# Top.net
KiCad netlist of a schematic drawn in Altium Designer
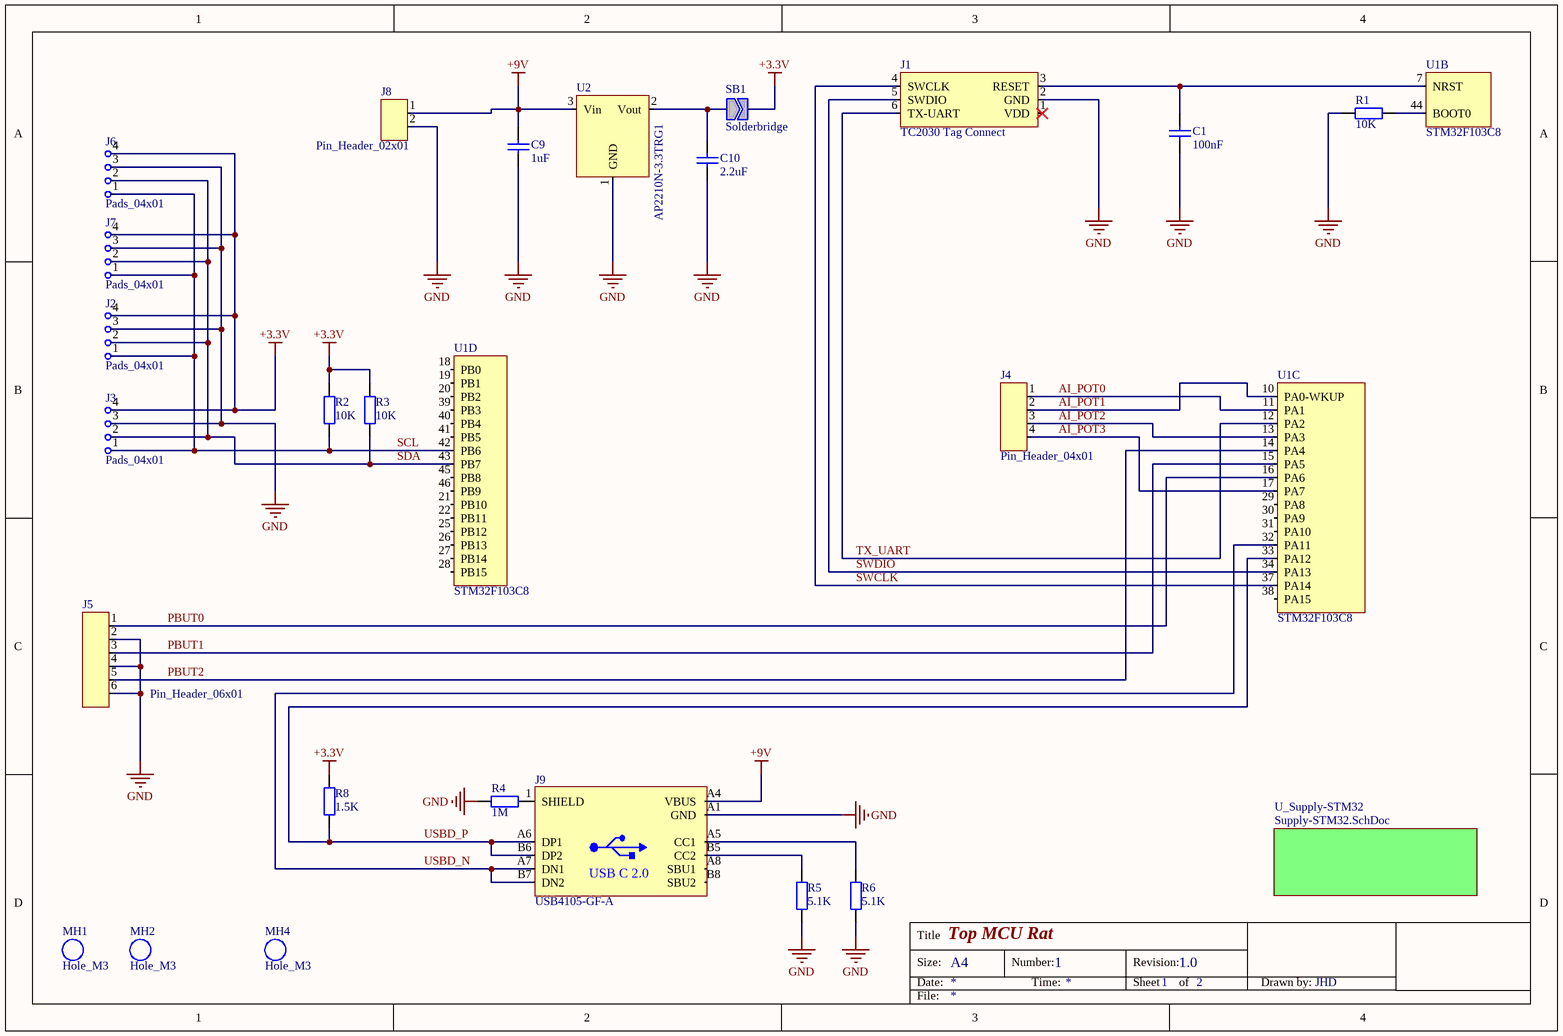
[diagram p0: Top.SchDoc]

(export (version "E")
  (design (tool "Eeschema 10.0.6"))
  (components
    (comp (ref "C1")
      (value "100nF")
      (footprint "CAP_0603")
      (fields (field (name "Comment") "CAP"))
      (libsource (lib "Passive") (part "CAP"))
    )
    (comp (ref "C9")
      (value "1uF")
      (footprint "CAP_0603")
      (fields (field (name "Comment") "CAP"))
      (libsource (lib "") (part "CAP_1"))
    )
    (comp (ref "C10")
      (value "2.2uF")
      (footprint "CAP_0603")
      (fields (field (name "Comment") "CAP"))
      (libsource (lib "") (part "CAP_1"))
    )
    (comp (ref "J1")
      (value "TC2030 Tag Connect")
      (footprint "TC2030-MCP")
      (libsource (lib "Connectors") (part "TC2030"))
    )
    (comp (ref "J2")
      (value "Pads_04x01")
      (footprint "04X01_PADS_2.54MM")
      (libsource (lib "Connectors") (part "Pads_04x01"))
    )
    (comp (ref "J3")
      (value "Pads_04x01")
      (footprint "04X01_PADS_2.54MM")
      (libsource (lib "Connectors") (part "Pads_04x01"))
    )
    (comp (ref "J4")
      (value "Pin_Header_04x01")
      (footprint "04x01_Header_2.54mm_MAL")
      (libsource (lib "Connectors") (part "Pin_Header_04x01"))
    )
    (comp (ref "J5")
      (value "Pin_Header_06x01")
      (footprint "06X01_TERM_5.00MM_FEM_DOWN")
      (libsource (lib "Connectors") (part "Pin_Header_06x01"))
    )
    (comp (ref "J6")
      (value "Pads_04x01")
      (footprint "04X01_PADS_2.54MM")
      (libsource (lib "Connectors") (part "Pads_04x01"))
    )
    (comp (ref "J7")
      (value "Pads_04x01")
      (footprint "04X01_PADS_2.54MM")
      (libsource (lib "Connectors") (part "Pads_04x01"))
    )
    (comp (ref "J8")
      (value "Pin_Header_02x01")
      (footprint "02X01_TERM_5.00MM_FEM_DOWN")
      (libsource (lib "Connectors") (part "Pin_Header_02x01"))
    )
    (comp (ref "J9")
      (value "USB4105-GF-A")
      (footprint "USB4105-GF-A")
      (description "USB Connectors USB Type C,2.0, Rec,SMT, 0.95mmTH Shell Stakes,G/F,RA,Top Mnt,T&R")
      (libsource (lib "GCT") (part "USB4105-GF-A"))
    )
    (comp (ref "MH1") (value "Hole_M3") (footprint "Hole_M3") (libsource (lib "Holes") (part "Hole_M3")))
    (comp (ref "MH2") (value "Hole_M3") (footprint "Hole_M3") (libsource (lib "Holes") (part "Hole_M3")))
    (comp (ref "MH4") (value "Hole_M3") (footprint "Hole_M3") (libsource (lib "Holes") (part "Hole_M3")))
    (comp (ref "R1")
      (value "10K")
      (footprint "RES_0603")
      (fields (field (name "Comment") "RES"))
      (libsource (lib "Passive") (part "RES"))
    )
    (comp (ref "R2")
      (value "10K")
      (footprint "RES_0603")
      (fields (field (name "Comment") "RES"))
      (libsource (lib "") (part "RES_1"))
    )
    (comp (ref "R3")
      (value "10K")
      (footprint "RES_0603")
      (fields (field (name "Comment") "RES"))
      (libsource (lib "") (part "RES_1"))
    )
    (comp (ref "R4")
      (value "1M")
      (footprint "RES_0603")
      (fields (field (name "Comment") "RES"))
      (libsource (lib "Passive") (part "RES"))
    )
    (comp (ref "R5")
      (value "5.1K")
      (footprint "RES_0603")
      (fields (field (name "Comment") "RES"))
      (libsource (lib "") (part "RES_1"))
    )
    (comp (ref "R6")
      (value "5.1K")
      (footprint "RES_0603")
      (fields (field (name "Comment") "RES"))
      (libsource (lib "") (part "RES_1"))
    )
    (comp (ref "R8")
      (value "1.5K")
      (footprint "RES_0603")
      (fields (field (name "Comment") "RES"))
      (libsource (lib "") (part "RES_1"))
    )
    (comp (ref "SB1")
      (value "Solderbridge")
      (footprint "TRIAN SOLDERBRIDGE")
      (libsource (lib "SolderJumper") (part "Solderbridge"))
    )
    (comp (ref "U1")
      (value "STM32F103C8")
      (footprint "LQFP48P05S97X97")
      (fields (field (name "MANUFACTURER") "STMicroelectronics"))
      (libsource (lib "ST") (part "STM32F103C8"))
    )
    (comp (ref "U2")
      (value "AP2210N-3.3TRG1")
      (footprint "SOT-23-3")
      (fields (field (name "MANUFACTURER") "Diodes Incorperated"))
      (libsource (lib "Diodes Incorporated") (part "AP2210N-3.3TRG1"))
    )
  )
  (nets
    (net (code "1") (name "+3.3V") (class "Default")
      (node (ref "J2") (pin "4") (pintype "passive"))
      (node (ref "J3") (pin "4") (pintype "passive"))
      (node (ref "J6") (pin "4") (pintype "passive"))
      (node (ref "J7") (pin "4") (pintype "passive"))
      (node (ref "R2") (pin "2") (pinfunction "2_2") (pintype "passive"))
      (node (ref "R3") (pin "2") (pinfunction "2_2") (pintype "passive"))
      (node (ref "R8") (pin "2") (pinfunction "2_2") (pintype "passive"))
      (node (ref "SB1") (pin "2") (pinfunction "2_2") (pintype "passive"))
    )
    (net (code "2") (name "+9V") (class "Default")
      (node (ref "C9") (pin "2") (pinfunction "2_2") (pintype "passive"))
      (node (ref "J8") (pin "1") (pintype "passive"))
      (node (ref "J9") (pin "A4") (pinfunction "VBUS_A4") (pintype "power_in"))
      (node (ref "U2") (pin "3") (pinfunction "Vin_3") (pintype "power_in"))
    )
    (net (code "3") (name "/AI_POT0") (class "Default")
      (node (ref "J4") (pin "1") (pintype "passive"))
      (node (ref "U1") (pin "11") (pinfunction "PA1_11") (pintype "bidirectional"))
    )
    (net (code "4") (name "/AI_POT1") (class "Default")
      (node (ref "J4") (pin "2") (pintype "passive"))
      (node (ref "U1") (pin "10") (pinfunction "PA0-WKUP_10") (pintype "bidirectional"))
    )
    (net (code "5") (name "/AI_POT2") (class "Default")
      (node (ref "J4") (pin "3") (pintype "passive"))
      (node (ref "U1") (pin "13") (pinfunction "PA3_13") (pintype "bidirectional"))
    )
    (net (code "6") (name "/AI_POT3") (class "Default")
      (node (ref "J4") (pin "4") (pintype "passive"))
      (node (ref "U1") (pin "17") (pinfunction "PA7_17") (pintype "bidirectional"))
    )
    (net (code "7") (name "/PBUT0") (class "Default")
      (node (ref "J5") (pin "1") (pintype "passive"))
      (node (ref "U1") (pin "16") (pinfunction "PA6_16") (pintype "bidirectional"))
    )
    (net (code "8") (name "/PBUT1") (class "Default")
      (node (ref "J5") (pin "3") (pintype "passive"))
      (node (ref "U1") (pin "15") (pinfunction "PA5_15") (pintype "bidirectional"))
    )
    (net (code "9") (name "/PBUT2") (class "Default")
      (node (ref "J5") (pin "5") (pintype "passive"))
      (node (ref "U1") (pin "14") (pinfunction "PA4_14") (pintype "bidirectional"))
    )
    (net (code "10") (name "/SCL") (class "Default")
      (node (ref "J2") (pin "1") (pintype "passive"))
      (node (ref "J3") (pin "1") (pintype "passive"))
      (node (ref "J6") (pin "1") (pintype "passive"))
      (node (ref "J7") (pin "1") (pintype "passive"))
      (node (ref "R2") (pin "1") (pinfunction "1_1") (pintype "passive"))
      (node (ref "U1") (pin "42") (pinfunction "PB6_42") (pintype "bidirectional"))
    )
    (net (code "11") (name "/SDA") (class "Default")
      (node (ref "J2") (pin "2") (pintype "passive"))
      (node (ref "J3") (pin "2") (pintype "passive"))
      (node (ref "J6") (pin "2") (pintype "passive"))
      (node (ref "J7") (pin "2") (pintype "passive"))
      (node (ref "R3") (pin "1") (pinfunction "1_1") (pintype "passive"))
      (node (ref "U1") (pin "43") (pinfunction "PB7_43") (pintype "bidirectional"))
    )
    (net (code "12") (name "/SWCLK") (class "Default")
      (node (ref "J1") (pin "4") (pinfunction "SWCLK_4") (pintype "passive"))
      (node (ref "U1") (pin "37") (pinfunction "PA14_37") (pintype "bidirectional"))
    )
    (net (code "13") (name "/SWDIO") (class "Default")
      (node (ref "J1") (pin "5") (pinfunction "SWDIO_5") (pintype "passive"))
      (node (ref "U1") (pin "34") (pinfunction "PA13_34") (pintype "bidirectional"))
    )
    (net (code "14") (name "/TX_UART") (class "Default")
      (node (ref "J1") (pin "6") (pinfunction "TX-UART_6") (pintype "passive"))
      (node (ref "U1") (pin "12") (pinfunction "PA2_12") (pintype "bidirectional"))
    )
    (net (code "15") (name "/USBD_N") (class "Default")
      (node (ref "J9") (pin "A7") (pinfunction "DN1_A7") (pintype "bidirectional"))
      (node (ref "J9") (pin "B7") (pinfunction "DN2_B7") (pintype "bidirectional"))
      (node (ref "U1") (pin "32") (pinfunction "PA11_32") (pintype "bidirectional"))
    )
    (net (code "16") (name "/USBD_P") (class "Default")
      (node (ref "J9") (pin "A6") (pinfunction "DP1_A6") (pintype "bidirectional"))
      (node (ref "J9") (pin "B6") (pinfunction "DP2_B6") (pintype "bidirectional"))
      (node (ref "R8") (pin "1") (pinfunction "1_1") (pintype "passive"))
      (node (ref "U1") (pin "33") (pinfunction "PA12_33") (pintype "bidirectional"))
    )
    (net (code "17") (name "GND") (class "Default")
      (node (ref "C1") (pin "1") (pinfunction "1_1") (pintype "passive"))
      (node (ref "C10") (pin "1") (pinfunction "1_1") (pintype "passive"))
      (node (ref "C9") (pin "1") (pinfunction "1_1") (pintype "passive"))
      (node (ref "J1") (pin "2") (pinfunction "GND_2") (pintype "passive"))
      (node (ref "J2") (pin "3") (pintype "passive"))
      (node (ref "J3") (pin "3") (pintype "passive"))
      (node (ref "J5") (pin "2") (pintype "passive"))
      (node (ref "J5") (pin "4") (pintype "passive"))
      (node (ref "J5") (pin "6") (pintype "passive"))
      (node (ref "J6") (pin "3") (pintype "passive"))
      (node (ref "J7") (pin "3") (pintype "passive"))
      (node (ref "J8") (pin "2") (pintype "passive"))
      (node (ref "J9") (pin "A1") (pinfunction "GND_A1") (pintype "power_in"))
      (node (ref "R1") (pin "2") (pinfunction "2_2") (pintype "passive"))
      (node (ref "R4") (pin "2") (pinfunction "2_2") (pintype "passive"))
      (node (ref "R5") (pin "1") (pinfunction "1_1") (pintype "passive"))
      (node (ref "R6") (pin "1") (pinfunction "1_1") (pintype "passive"))
      (node (ref "U2") (pin "1") (pinfunction "GND_1") (pintype "power_in"))
    )
    (net (code "18") (name "Net-(J1-RESET)") (class "Default")
      (node (ref "C1") (pin "2") (pinfunction "2_2") (pintype "passive"))
      (node (ref "J1") (pin "3") (pinfunction "RESET_3") (pintype "passive"))
      (node (ref "U1") (pin "7") (pinfunction "NRST_7") (pintype "bidirectional"))
    )
    (net (code "19") (name "Net-(J9-CC1)") (class "Default")
      (node (ref "J9") (pin "A5") (pinfunction "CC1_A5") (pintype "passive"))
      (node (ref "R6") (pin "2") (pinfunction "2_2") (pintype "passive"))
    )
    (net (code "20") (name "Net-(J9-CC2)") (class "Default")
      (node (ref "J9") (pin "B5") (pinfunction "CC2_B5") (pintype "passive"))
      (node (ref "R5") (pin "2") (pinfunction "2_2") (pintype "passive"))
    )
    (net (code "21") (name "Net-(J9-SHIELD)") (class "Default")
      (node (ref "J9") (pin "1") (pinfunction "SHIELD_1") (pintype "passive"))
      (node (ref "R4") (pin "1") (pinfunction "1_1") (pintype "passive"))
    )
    (net (code "22") (name "Net-(U1B-BOOT0)") (class "Default")
      (node (ref "R1") (pin "1") (pinfunction "1_1") (pintype "passive"))
      (node (ref "U1") (pin "44") (pinfunction "BOOT0_44") (pintype "input"))
    )
    (net (code "23") (name "Net-(U2-Vout)") (class "Default")
      (node (ref "C10") (pin "2") (pinfunction "2_2") (pintype "passive"))
      (node (ref "SB1") (pin "1") (pinfunction "1_1") (pintype "passive"))
      (node (ref "U2") (pin "2") (pinfunction "Vout_2") (pintype "power_in"))
    )
    (net (code "24") (name "unconnected-(J1-VDD-Pad1)") (class "Default")
      (node (ref "J1") (pin "1") (pinfunction "VDD_1") (pintype "passive+no_connect"))
    )
    (net (code "25") (name "unconnected-(J9-SBU1-PadA8)") (class "Default")
      (node (ref "J9") (pin "A8") (pinfunction "SBU1_A8") (pintype "passive"))
    )
    (net (code "26") (name "unconnected-(J9-SBU2-PadB8)") (class "Default")
      (node (ref "J9") (pin "B8") (pinfunction "SBU2_B8") (pintype "passive"))
    )
    (net (code "27") (name "unconnected-(U1C-PA8-Pad29)") (class "Default")
      (node (ref "U1") (pin "29") (pinfunction "PA8_29") (pintype "bidirectional"))
    )
    (net (code "28") (name "unconnected-(U1C-PA9-Pad30)") (class "Default")
      (node (ref "U1") (pin "30") (pinfunction "PA9_30") (pintype "bidirectional"))
    )
    (net (code "29") (name "unconnected-(U1C-PA10-Pad31)") (class "Default")
      (node (ref "U1") (pin "31") (pinfunction "PA10_31") (pintype "bidirectional"))
    )
    (net (code "30") (name "unconnected-(U1C-PA15-Pad38)") (class "Default")
      (node (ref "U1") (pin "38") (pinfunction "PA15_38") (pintype "bidirectional"))
    )
    (net (code "31") (name "unconnected-(U1D-PB0-Pad18)") (class "Default")
      (node (ref "U1") (pin "18") (pinfunction "PB0_18") (pintype "bidirectional"))
    )
    (net (code "32") (name "unconnected-(U1D-PB1-Pad19)") (class "Default")
      (node (ref "U1") (pin "19") (pinfunction "PB1_19") (pintype "bidirectional"))
    )
    (net (code "33") (name "unconnected-(U1D-PB2-Pad20)") (class "Default")
      (node (ref "U1") (pin "20") (pinfunction "PB2_20") (pintype "bidirectional"))
    )
    (net (code "34") (name "unconnected-(U1D-PB3-Pad39)") (class "Default")
      (node (ref "U1") (pin "39") (pinfunction "PB3_39") (pintype "bidirectional"))
    )
    (net (code "35") (name "unconnected-(U1D-PB4-Pad40)") (class "Default")
      (node (ref "U1") (pin "40") (pinfunction "PB4_40") (pintype "bidirectional"))
    )
    (net (code "36") (name "unconnected-(U1D-PB5-Pad41)") (class "Default")
      (node (ref "U1") (pin "41") (pinfunction "PB5_41") (pintype "bidirectional"))
    )
    (net (code "37") (name "unconnected-(U1D-PB8-Pad45)") (class "Default")
      (node (ref "U1") (pin "45") (pinfunction "PB8_45") (pintype "bidirectional"))
    )
    (net (code "38") (name "unconnected-(U1D-PB9-Pad46)") (class "Default")
      (node (ref "U1") (pin "46") (pinfunction "PB9_46") (pintype "bidirectional"))
    )
    (net (code "39") (name "unconnected-(U1D-PB10-Pad21)") (class "Default")
      (node (ref "U1") (pin "21") (pinfunction "PB10_21") (pintype "bidirectional"))
    )
    (net (code "40") (name "unconnected-(U1D-PB11-Pad22)") (class "Default")
      (node (ref "U1") (pin "22") (pinfunction "PB11_22") (pintype "bidirectional"))
    )
    (net (code "41") (name "unconnected-(U1D-PB12-Pad25)") (class "Default")
      (node (ref "U1") (pin "25") (pinfunction "PB12_25") (pintype "bidirectional"))
    )
    (net (code "42") (name "unconnected-(U1D-PB13-Pad26)") (class "Default")
      (node (ref "U1") (pin "26") (pinfunction "PB13_26") (pintype "bidirectional"))
    )
    (net (code "43") (name "unconnected-(U1D-PB14-Pad27)") (class "Default")
      (node (ref "U1") (pin "27") (pinfunction "PB14_27") (pintype "bidirectional"))
    )
    (net (code "44") (name "unconnected-(U1D-PB15-Pad28)") (class "Default")
      (node (ref "U1") (pin "28") (pinfunction "PB15_28") (pintype "bidirectional"))
    )
  )
)
